# water_level_v3.net
KiCad netlist of a schematic drawn in Altium Designer
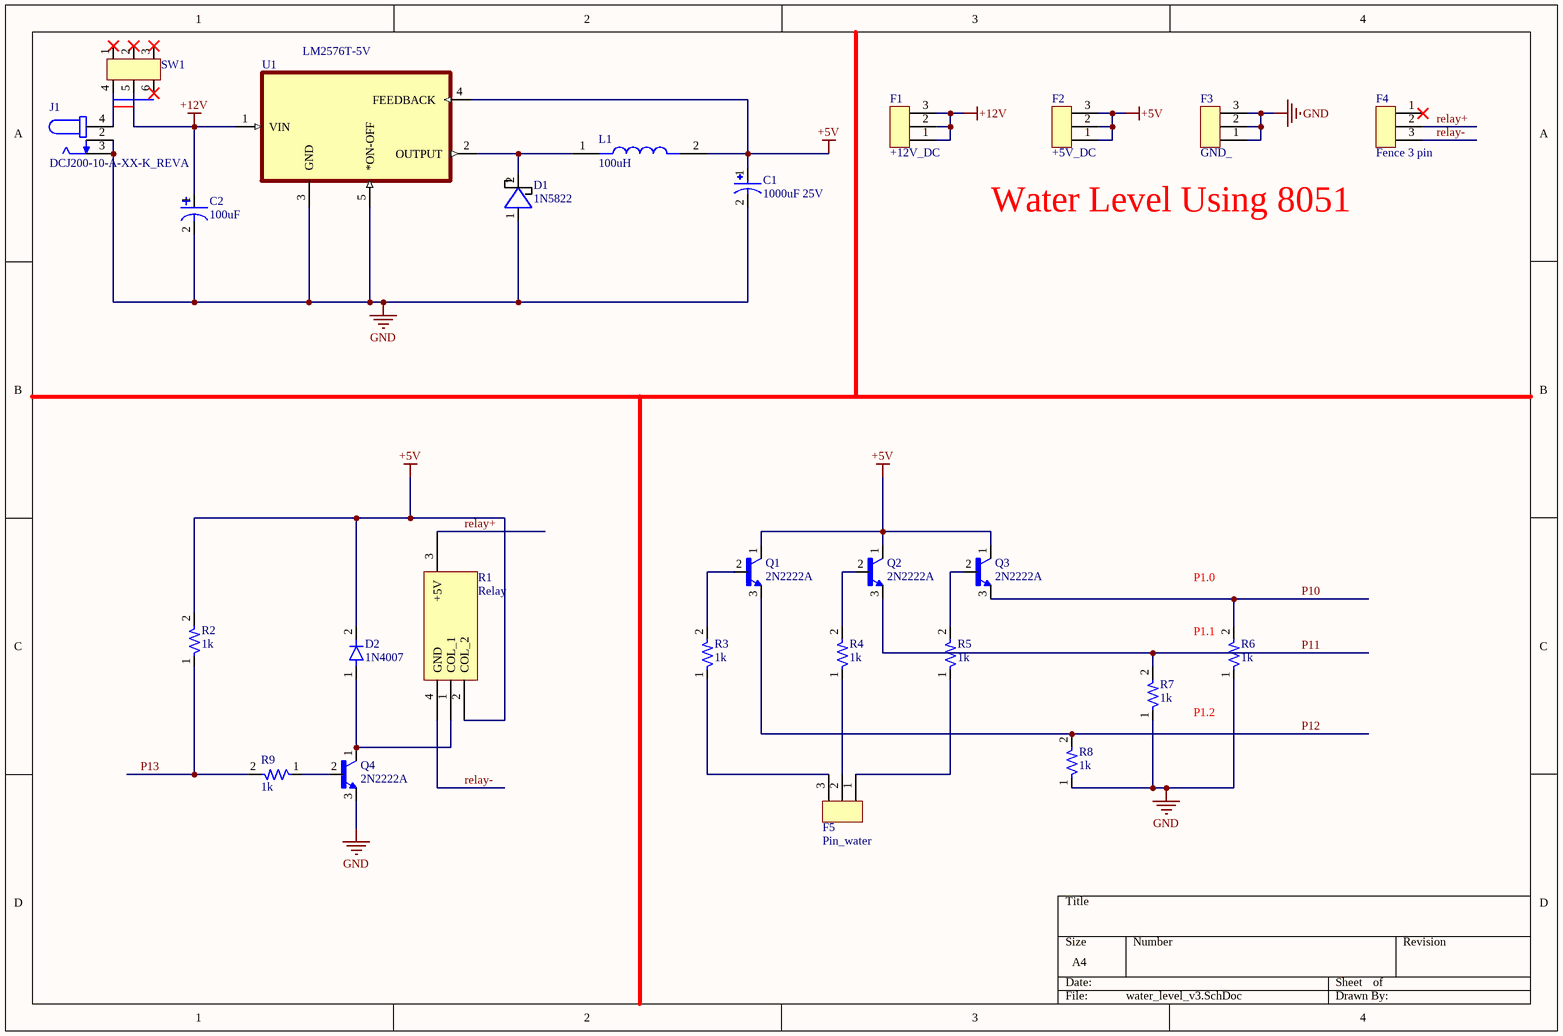
[diagram p0: water_level_v3.SchDoc]

(export (version "E")
  (design (tool "Eeschema 10.0.6"))
  (components
    (comp (ref "C1")
      (value "1000uF 25V")
      (footprint "PcbLib2:Capacitor 1000uF 25V")
      (description "Tụ hóa 1000uF 25V\r\nKích thước 10x17mm")
      (fields (field (name "MF") "{'manufacturer': u'Panasonic'}") (field (name "MP") "EEUTA1V101"))
      (libsource (lib "Schlib2") (part "Capacitor 1000uF 25V"))
    )
    (comp (ref "C2")
      (value "100uF")
      (footprint "PcbLib2:Capacitor 100uF 35V")
      (description "Tụ hóa 100uF 35V")
      (libsource (lib "Schlib2") (part "Capacitor 100uF"))
    )
    (comp (ref "D1")
      (value "1N5822")
      (footprint "PcbLib2:Diode 1N5822")
      (description "1N5822 Diode Schottky 40V 3A DO-201AD\r\n(Through hole)")
      (libsource (lib "Schlib2") (part "Diode 1N5822"))
    )
    (comp (ref "D2")
      (value "1N4007")
      (footprint "PcbLib2:1N4007")
      (description "Diode 1N4007 1A 1000V DIP")
      (libsource (lib "Schlib2") (part "1N4007"))
    )
    (comp (ref "F1")
      (value "+12V_DC")
      (footprint "PcbLib2:Fence 3pin")
      (description "hàng rào male 6 chân")
      (libsource (lib "Schlib2") (part "Fence 3 pin"))
    )
    (comp (ref "F2")
      (value "+5V_DC")
      (footprint "PcbLib2:Fence 3pin")
      (description "hàng rào male 6 chân")
      (libsource (lib "Schlib2") (part "Fence 3 pin"))
    )
    (comp (ref "F3")
      (value "GND_")
      (footprint "PcbLib2:Fence 3pin")
      (description "hàng rào male 6 chân")
      (libsource (lib "Schlib2") (part "Fence 3 pin"))
    )
    (comp (ref "F4")
      (value "Fence 3 pin")
      (footprint "PcbLib2:Fence 3pin")
      (description "hàng rào male 6 chân")
      (libsource (lib "") (part "Fence 3 pin_1"))
    )
    (comp (ref "F5")
      (value "Pin_water")
      (footprint "PcbLib2:Fence 3pin")
      (description "hàng rào male 6 chân")
      (libsource (lib "") (part "Fence 3 pin_1"))
    )
    (comp (ref "J1")
      (value "DCJ200-10-A-XX-K_REVA")
      (footprint "GCT_DCJ200-10-A-XX-K_REVA")
      (description "Power Barrel Connector Jack 2.05mm ID (0.081), 5.50mm OD (0.217) Through Hole, Right Angle")
      (fields (field (name "MF") "Global Connector Technology") (field (name "MP") "DCJ200-10-A-K1-K"))
      (libsource (lib "Schlib2") (part "DCJ200-10-A-XX-K_REVA"))
    )
    (comp (ref "L1")
      (value "100uH")
      (footprint "PcbLib2:Inductor")
      (description "Cuộn cảm 100uH 0810 8x15mm")
      (libsource (lib "Schlib2") (part "Inductor"))
    )
    (comp (ref "Q1")
      (value "2N2222A")
      (footprint "PcbLib2:2N2222")
      (fields (field (name "MF") "{'manufacturer': u'Diotec Semiconductor'}"))
      (libsource (lib "Schlib2") (part "2N2222A"))
    )
    (comp (ref "Q2")
      (value "2N2222A")
      (footprint "PcbLib2:2N2222")
      (fields (field (name "MF") "{'manufacturer': u'Diotec Semiconductor'}"))
      (libsource (lib "Schlib2") (part "2N2222A"))
    )
    (comp (ref "Q3")
      (value "2N2222A")
      (footprint "PcbLib2:2N2222")
      (fields (field (name "MF") "{'manufacturer': u'Diotec Semiconductor'}"))
      (libsource (lib "Schlib2") (part "2N2222A"))
    )
    (comp (ref "Q4")
      (value "2N2222A")
      (footprint "PcbLib2:2N2222")
      (fields (field (name "MF") "{'manufacturer': u'Diotec Semiconductor'}"))
      (libsource (lib "Schlib2") (part "2N2222A"))
    )
    (comp (ref "R1")
      (value "Relay")
      (footprint "Relay")
      (description "Relay 5V5A HF46F-G 5-HS1 của Hongfa.\r\nVẽ dựa trên HF46F/005-HS1F(610) của Hongfa")
      (libsource (lib "Schlib2") (part "Relay"))
    )
    (comp (ref "R2")
      (value "1k")
      (footprint "PcbLib2:RESISTOR 1W")
      (description "dien tro")
      (libsource (lib "Schlib2") (part "Resistor"))
    )
    (comp (ref "R3")
      (value "1k")
      (footprint "PcbLib2:RESISTOR 1W")
      (description "dien tro")
      (libsource (lib "Schlib2") (part "Resistor"))
    )
    (comp (ref "R4")
      (value "1k")
      (footprint "PcbLib2:RESISTOR 1W")
      (description "dien tro")
      (libsource (lib "Schlib2") (part "Resistor"))
    )
    (comp (ref "R5")
      (value "1k")
      (footprint "PcbLib2:RESISTOR 1W")
      (description "dien tro")
      (libsource (lib "Schlib2") (part "Resistor"))
    )
    (comp (ref "R6")
      (value "1k")
      (footprint "PcbLib2:RESISTOR 1W")
      (description "dien tro")
      (libsource (lib "Schlib2") (part "Resistor"))
    )
    (comp (ref "R7")
      (value "1k")
      (footprint "PcbLib2:RESISTOR 1W")
      (description "dien tro")
      (libsource (lib "Schlib2") (part "Resistor"))
    )
    (comp (ref "R8")
      (value "1k")
      (footprint "PcbLib2:RESISTOR 1W")
      (description "dien tro")
      (libsource (lib "Schlib2") (part "Resistor"))
    )
    (comp (ref "R9")
      (value "1k")
      (footprint "PcbLib2:RESISTOR 1W")
      (description "dien tro")
      (libsource (lib "Schlib2") (part "Resistor"))
    )
    (comp (ref "SW1")
      (value "Push_sw 8x8mm 6pin")
      (footprint "PUSH_SW 6PIN")
      (description "6pin free 1-3.4-6 push 2-3,4-5")
      (libsource (lib "Schlib2") (part "Push_sw 8x8mm 6pin"))
    )
    (comp (ref "U1")
      (value "LM2576T-5V")
      (footprint "PcbLib2:LM2596T-5V")
      (description "IC, STEP-DOWN VOLTAGE REGULATOR")
      (fields (field (name "MF") "{'manufacturer': u'Texas Instruments'}") (field (name "MP") "LM2596T-12"))
      (libsource (lib "Schlib2") (part "LM2596T-5V"))
    )
  )
  (nets
    (net (code "1") (name "+5V") (class "Default")
      (node (ref "C1") (pin "1") (pinfunction "1_1") (pintype "passive"))
      (node (ref "D2") (pin "2") (pinfunction "2_2") (pintype "passive"))
      (node (ref "F2") (pin "1") (pinfunction "1_1") (pintype "passive"))
      (node (ref "F2") (pin "2") (pinfunction "2_2") (pintype "passive"))
      (node (ref "F2") (pin "3") (pinfunction "3_3") (pintype "passive"))
      (node (ref "L1") (pin "2") (pinfunction "2_2") (pintype "passive"))
      (node (ref "Q1") (pin "1") (pinfunction "C_1") (pintype "passive"))
      (node (ref "Q2") (pin "1") (pinfunction "C_1") (pintype "passive"))
      (node (ref "Q3") (pin "1") (pinfunction "C_1") (pintype "passive"))
      (node (ref "R1") (pin "2") (pinfunction "COL_2_2") (pintype "passive"))
      (node (ref "R2") (pin "2") (pinfunction "2_2") (pintype "passive"))
      (node (ref "U1") (pin "4") (pinfunction "FEEDBACK_4") (pintype "input"))
    )
    (net (code "2") (name "+12V") (class "Default")
      (node (ref "C2") (pin "1") (pinfunction "1_1") (pintype "passive"))
      (node (ref "F1") (pin "1") (pinfunction "1_1") (pintype "passive"))
      (node (ref "F1") (pin "2") (pinfunction "2_2") (pintype "passive"))
      (node (ref "F1") (pin "3") (pinfunction "3_3") (pintype "passive"))
      (node (ref "SW1") (pin "5") (pinfunction "5_5") (pintype "passive"))
      (node (ref "U1") (pin "1") (pinfunction "VIN_1") (pintype "input"))
    )
    (net (code "3") (name "/P10") (class "Default")
      (node (ref "Q3") (pin "3") (pinfunction "E_3") (pintype "passive"))
      (node (ref "R6") (pin "2") (pinfunction "2_2") (pintype "passive"))
    )
    (net (code "4") (name "/P11") (class "Default")
      (node (ref "Q2") (pin "3") (pinfunction "E_3") (pintype "passive"))
      (node (ref "R7") (pin "2") (pinfunction "2_2") (pintype "passive"))
    )
    (net (code "5") (name "/P12") (class "Default")
      (node (ref "Q1") (pin "3") (pinfunction "E_3") (pintype "passive"))
      (node (ref "R8") (pin "2") (pinfunction "2_2") (pintype "passive"))
    )
    (net (code "6") (name "/P13") (class "Default")
      (node (ref "R2") (pin "1") (pinfunction "1_1") (pintype "passive"))
      (node (ref "R9") (pin "2") (pinfunction "2_2") (pintype "passive"))
    )
    (net (code "7") (name "/relay+") (class "Default")
      (node (ref "F4") (pin "2") (pinfunction "2_2") (pintype "passive"))
      (node (ref "R1") (pin "3") (pinfunction "+5V_3") (pintype "passive"))
    )
    (net (code "8") (name "/relay-") (class "Default")
      (node (ref "F4") (pin "3") (pinfunction "3_3") (pintype "passive"))
      (node (ref "R1") (pin "4") (pinfunction "GND_4") (pintype "passive"))
    )
    (net (code "9") (name "GND") (class "Default")
      (node (ref "C1") (pin "2") (pinfunction "2_2") (pintype "passive"))
      (node (ref "C2") (pin "2") (pinfunction "2_2") (pintype "passive"))
      (node (ref "D1") (pin "1") (pinfunction "1_1") (pintype "passive"))
      (node (ref "F3") (pin "1") (pinfunction "1_1") (pintype "passive"))
      (node (ref "F3") (pin "2") (pinfunction "2_2") (pintype "passive"))
      (node (ref "F3") (pin "3") (pinfunction "3_3") (pintype "passive"))
      (node (ref "J1") (pin "2") (pinfunction "2_2") (pintype "passive"))
      (node (ref "J1") (pin "3") (pinfunction "3_3") (pintype "passive"))
      (node (ref "Q4") (pin "3") (pinfunction "E_3") (pintype "passive"))
      (node (ref "R6") (pin "1") (pinfunction "1_1") (pintype "passive"))
      (node (ref "R7") (pin "1") (pinfunction "1_1") (pintype "passive"))
      (node (ref "R8") (pin "1") (pinfunction "1_1") (pintype "passive"))
      (node (ref "U1") (pin "3") (pinfunction "GND_3") (pintype "passive"))
      (node (ref "U1") (pin "5") (pinfunction "*ON-OFF_5") (pintype "input"))
    )
    (net (code "10") (name "Net-(F5-Pad1)") (class "Default")
      (node (ref "F5") (pin "1") (pinfunction "1_1") (pintype "passive"))
      (node (ref "R5") (pin "1") (pinfunction "1_1") (pintype "passive"))
    )
    (net (code "11") (name "Net-(F5-Pad2)") (class "Default")
      (node (ref "F5") (pin "2") (pinfunction "2_2") (pintype "passive"))
      (node (ref "R4") (pin "1") (pinfunction "1_1") (pintype "passive"))
    )
    (net (code "12") (name "Net-(F5-Pad3)") (class "Default")
      (node (ref "F5") (pin "3") (pinfunction "3_3") (pintype "passive"))
      (node (ref "R3") (pin "1") (pinfunction "1_1") (pintype "passive"))
    )
    (net (code "13") (name "Net-(J1-1)") (class "Default")
      (node (ref "J1") (pin "4") (pinfunction "1_4") (pintype "passive"))
      (node (ref "SW1") (pin "4") (pinfunction "4_4") (pintype "passive"))
    )
    (net (code "14") (name "Net-(Q1-B)") (class "Default")
      (node (ref "Q1") (pin "2") (pinfunction "B_2") (pintype "passive"))
      (node (ref "R3") (pin "2") (pinfunction "2_2") (pintype "passive"))
    )
    (net (code "15") (name "Net-(Q2-B)") (class "Default")
      (node (ref "Q2") (pin "2") (pinfunction "B_2") (pintype "passive"))
      (node (ref "R4") (pin "2") (pinfunction "2_2") (pintype "passive"))
    )
    (net (code "16") (name "Net-(Q3-B)") (class "Default")
      (node (ref "Q3") (pin "2") (pinfunction "B_2") (pintype "passive"))
      (node (ref "R5") (pin "2") (pinfunction "2_2") (pintype "passive"))
    )
    (net (code "17") (name "Net-(Q4-B)") (class "Default")
      (node (ref "Q4") (pin "2") (pinfunction "B_2") (pintype "passive"))
      (node (ref "R9") (pin "1") (pinfunction "1_1") (pintype "passive"))
    )
    (net (code "18") (name "Net-(Q4-C)") (class "Default")
      (node (ref "D2") (pin "1") (pinfunction "1_1") (pintype "passive"))
      (node (ref "Q4") (pin "1") (pinfunction "C_1") (pintype "passive"))
      (node (ref "R1") (pin "1") (pinfunction "COL_1_1") (pintype "passive"))
    )
    (net (code "19") (name "Net-(U1-OUTPUT)") (class "Default")
      (node (ref "D1") (pin "2") (pinfunction "2_2") (pintype "passive"))
      (node (ref "L1") (pin "1") (pinfunction "1_1") (pintype "passive"))
      (node (ref "U1") (pin "2") (pinfunction "OUTPUT_2") (pintype "output"))
    )
    (net (code "20") (name "unconnected-(F4-Pad1)") (class "Default")
      (node (ref "F4") (pin "1") (pinfunction "1_1") (pintype "passive+no_connect"))
    )
    (net (code "21") (name "unconnected-(SW1-Pad1)") (class "Default")
      (node (ref "SW1") (pin "1") (pinfunction "1_1") (pintype "passive+no_connect"))
    )
    (net (code "22") (name "unconnected-(SW1-Pad2)") (class "Default")
      (node (ref "SW1") (pin "2") (pinfunction "2_2") (pintype "passive+no_connect"))
    )
    (net (code "23") (name "unconnected-(SW1-Pad3)") (class "Default")
      (node (ref "SW1") (pin "3") (pinfunction "3_3") (pintype "passive+no_connect"))
    )
    (net (code "24") (name "unconnected-(SW1-Pad6)") (class "Default")
      (node (ref "SW1") (pin "6") (pinfunction "6_6") (pintype "passive+no_connect"))
    )
  )
)
